# 2_MCU.net
KiCad netlist of a schematic drawn in Altium Designer
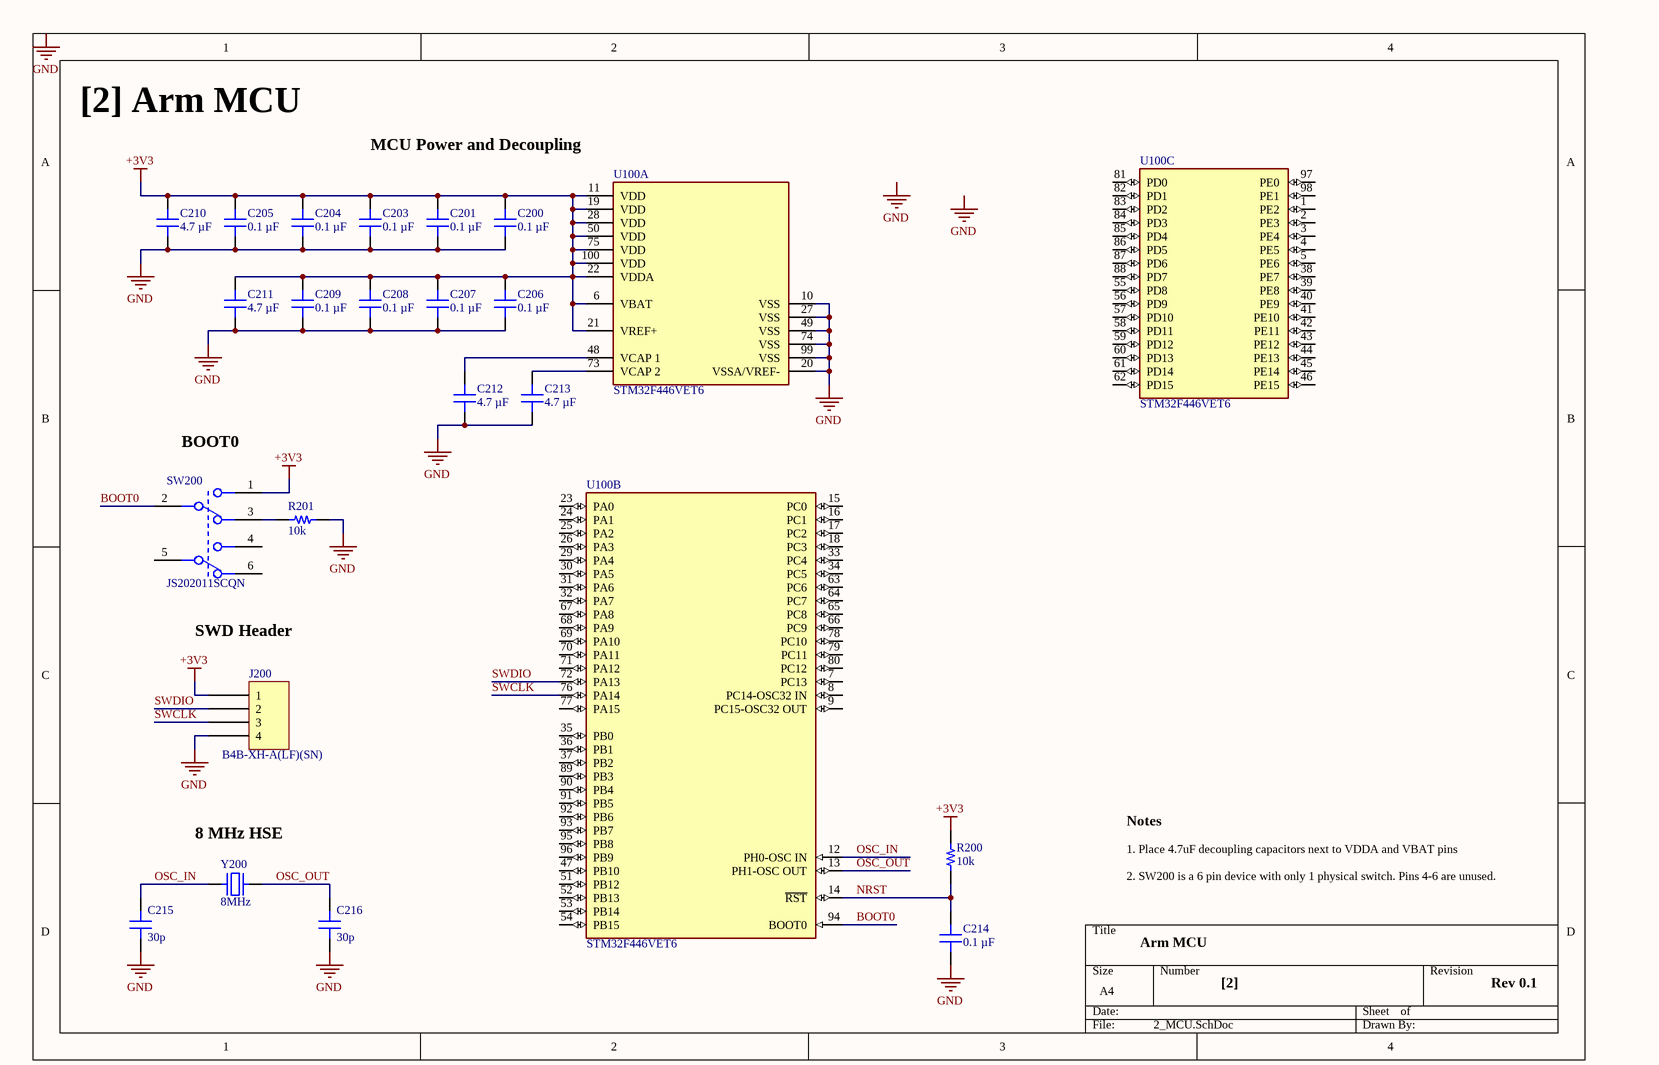
[diagram p0: 2_MCU.SchDoc]

(export (version "E")
  (design (tool "Eeschema 10.0.6"))
  (components
    (comp (ref "C200")
      (value "0.1 µF")
      (footprint "CAP 0603_1608")
      (description "CAP CER 0.1UF 50V X7R 0603")
      (fields
        (field (name "PART NUMBER") "C0603C104K5RAC7411")
        (field (name "CAPACITANCE") "0.1 µF")
        (field (name "MANUFACTURER") "KEMET")
      )
      (libsource (lib "Celestial Altium Library - altium_library") (part "Capacitor"))
    )
    (comp (ref "C201")
      (value "0.1 µF")
      (footprint "CAP 0603_1608")
      (description "CAP CER 0.1UF 50V X7R 0603")
      (fields
        (field (name "PART NUMBER") "C0603C104K5RAC7411")
        (field (name "CAPACITANCE") "0.1 µF")
        (field (name "MANUFACTURER") "KEMET")
      )
      (libsource (lib "Celestial Altium Library - altium_library") (part "Capacitor"))
    )
    (comp (ref "C203")
      (value "0.1 µF")
      (footprint "CAP 0603_1608")
      (description "CAP CER 0.1UF 50V X7R 0603")
      (fields
        (field (name "PART NUMBER") "C0603C104K5RAC7411")
        (field (name "CAPACITANCE") "0.1 µF")
        (field (name "MANUFACTURER") "KEMET")
      )
      (libsource (lib "Celestial Altium Library - altium_library") (part "Capacitor"))
    )
    (comp (ref "C204")
      (value "0.1 µF")
      (footprint "CAP 0603_1608")
      (description "CAP CER 0.1UF 50V X7R 0603")
      (fields
        (field (name "PART NUMBER") "C0603C104K5RAC7411")
        (field (name "CAPACITANCE") "0.1 µF")
        (field (name "MANUFACTURER") "KEMET")
      )
      (libsource (lib "Celestial Altium Library - altium_library") (part "Capacitor"))
    )
    (comp (ref "C205")
      (value "0.1 µF")
      (footprint "CAP 0603_1608")
      (description "CAP CER 0.1UF 50V X7R 0603")
      (fields
        (field (name "PART NUMBER") "C0603C104K5RAC7411")
        (field (name "CAPACITANCE") "0.1 µF")
        (field (name "MANUFACTURER") "KEMET")
      )
      (libsource (lib "Celestial Altium Library - altium_library") (part "Capacitor"))
    )
    (comp (ref "C206")
      (value "0.1 µF")
      (footprint "CAP 0603_1608")
      (description "CAP CER 0.1UF 50V X7R 0603")
      (fields
        (field (name "PART NUMBER") "C0603C104K5RAC7411")
        (field (name "CAPACITANCE") "0.1 µF")
        (field (name "MANUFACTURER") "KEMET")
      )
      (libsource (lib "Celestial Altium Library - altium_library") (part "Capacitor"))
    )
    (comp (ref "C207")
      (value "0.1 µF")
      (footprint "CAP 0603_1608")
      (description "CAP CER 0.1UF 50V X7R 0603")
      (fields
        (field (name "PART NUMBER") "C0603C104K5RAC7411")
        (field (name "CAPACITANCE") "0.1 µF")
        (field (name "MANUFACTURER") "KEMET")
      )
      (libsource (lib "Celestial Altium Library - altium_library") (part "Capacitor"))
    )
    (comp (ref "C208")
      (value "0.1 µF")
      (footprint "CAP 0603_1608")
      (description "CAP CER 0.1UF 50V X7R 0603")
      (fields
        (field (name "PART NUMBER") "C0603C104K5RAC7411")
        (field (name "CAPACITANCE") "0.1 µF")
        (field (name "MANUFACTURER") "KEMET")
      )
      (libsource (lib "Celestial Altium Library - altium_library") (part "Capacitor"))
    )
    (comp (ref "C209")
      (value "0.1 µF")
      (footprint "CAP 0603_1608")
      (description "CAP CER 0.1UF 50V X7R 0603")
      (fields
        (field (name "PART NUMBER") "C0603C104K5RAC7411")
        (field (name "CAPACITANCE") "0.1 µF")
        (field (name "MANUFACTURER") "KEMET")
      )
      (libsource (lib "Celestial Altium Library - altium_library") (part "Capacitor"))
    )
    (comp (ref "C210")
      (value "4.7 µF")
      (footprint "CAP 0805_2012")
      (description "CAP CER 4.7UF 25V X7R 0805")
      (fields
        (field (name "PART NUMBER") "C0805X475M3RACAUTO")
        (field (name "CAPACITANCE") "4.7 µF")
        (field (name "MANUFACTURER") "KEMET")
      )
      (libsource (lib "Celestial Altium Library - altium_library") (part "Capacitor"))
    )
    (comp (ref "C211")
      (value "4.7 µF")
      (footprint "CAP 0805_2012")
      (description "CAP CER 4.7UF 25V X7R 0805")
      (fields
        (field (name "PART NUMBER") "C0805X475M3RACAUTO")
        (field (name "CAPACITANCE") "4.7 µF")
        (field (name "MANUFACTURER") "KEMET")
      )
      (libsource (lib "Celestial Altium Library - altium_library") (part "Capacitor"))
    )
    (comp (ref "C212")
      (value "4.7 µF")
      (footprint "CAP 0805_2012")
      (description "CAP CER 4.7UF 25V X7R 0805")
      (fields
        (field (name "PART NUMBER") "C0805X475M3RACAUTO")
        (field (name "CAPACITANCE") "4.7 µF")
        (field (name "MANUFACTURER") "KEMET")
      )
      (libsource (lib "Celestial Altium Library - altium_library") (part "Capacitor"))
    )
    (comp (ref "C213")
      (value "4.7 µF")
      (footprint "CAP 0805_2012")
      (description "CAP CER 4.7UF 25V X7R 0805")
      (fields
        (field (name "PART NUMBER") "C0805X475M3RACAUTO")
        (field (name "CAPACITANCE") "4.7 µF")
        (field (name "MANUFACTURER") "KEMET")
      )
      (libsource (lib "Celestial Altium Library - altium_library") (part "Capacitor"))
    )
    (comp (ref "C214")
      (value "0.1 µF")
      (footprint "CAP 0603_1608")
      (description "CAP CER 0.1UF 50V X7R 0603")
      (fields
        (field (name "PART NUMBER") "C0603C104K5RAC7411")
        (field (name "CAPACITANCE") "0.1 µF")
        (field (name "MANUFACTURER") "KEMET")
      )
      (libsource (lib "Celestial Altium Library - altium_library") (part "Capacitor"))
    )
    (comp (ref "C215")
      (value "30p")
      (footprint "CAP 0603_1608")
      (description "CAP CER 30PF 50V C0G/NPO 0603")
      (fields (field (name "PART NUMBER") "CC0603GRNPO9BN300") (field (name "MANUFACTURER") "Yageo"))
      (libsource (lib "Celestial Altium Library - altium_library") (part "Capacitor"))
    )
    (comp (ref "C216")
      (value "30p")
      (footprint "CAP 0603_1608")
      (description "CAP CER 30PF 50V C0G/NPO 0603")
      (fields (field (name "PART NUMBER") "CC0603GRNPO9BN300") (field (name "MANUFACTURER") "Yageo"))
      (libsource (lib "Celestial Altium Library - altium_library") (part "Capacitor"))
    )
    (comp (ref "J200")
      (value "B4B-XH-A(LF)(SN)")
      (footprint "JST XH B4B-XH-A")
      (description "CONN HEADER VERT 4POS 2.5MM")
      (fields (field (name "MANUFACTURER") "JST Sales America Inc."))
      (libsource (lib "Celestial Altium Library - altium_library") (part "4 Pin"))
    )
    (comp (ref "R200")
      (value "10k")
      (footprint "RES 0603_1608")
      (description "RES 10K OHM 0.1% 1/16W 0603")
      (fields
        (field (name "PART NUMBER") "RNCS0603BKE10K0")
        (field (name "MANUFACTURER") "Stackpole Electronics Inc")
      )
      (libsource (lib "Celestial Altium Library - altium_library") (part "Resistor"))
    )
    (comp (ref "R201")
      (value "10k")
      (footprint "RES 0603_1608")
      (description "RES 10K OHM 0.1% 1/16W 0603")
      (fields
        (field (name "PART NUMBER") "RNCS0603BKE10K0")
        (field (name "MANUFACTURER") "Stackpole Electronics Inc")
      )
      (libsource (lib "Celestial Altium Library - altium_library") (part "Resistor"))
    )
    (comp (ref "SW200")
      (value "JS202011SCQN")
      (footprint "FP-JS202011SCQN-MFG")
      (description "SWITCH SLIDE DPDT 300MA 6V")
      (libsource (lib "Altium Content Vault") (part "ac99ea1af431c19115f5225061c5c88"))
    )
    (comp (ref "U100")
      (value "STM32F446VET6")
      (footprint "FP-LQFP100-1L-MFG")
      (description "IC MCU 32BIT 512KB FLASH 100LQFP")
      (fields
        (field (name "OCTOPART") "https://octopart.com/stm32f446vet6-stmicroelectronics-52642922")
        (field (name "MANUFACTURER") "STMicroelectronics")
      )
      (libsource (lib "Altium Content Vault") (part "8e3e88e6cb74ec1f9e49940598abbc7"))
    )
    (comp (ref "Y200")
      (value "8MHz")
      (footprint "TXC 9C")
      (description "CRYSTAL 8.0000MHZ 20PF SMD")
      (fields (field (name "PART NUMBER") "9C-8.000MBBK-T") (field (name "MANUFACTURER") "TXC CORPORATION"))
      (libsource (lib "Celestial Altium Library - altium_library") (part "TXC Crystal 9C"))
    )
  )
  (nets
    (net (code "1") (name "+3V3") (class "Default")
      (node (ref "C200") (pin "2") (pinfunction "2_2") (pintype "passive"))
      (node (ref "C201") (pin "2") (pinfunction "2_2") (pintype "passive"))
      (node (ref "C203") (pin "2") (pinfunction "2_2") (pintype "passive"))
      (node (ref "C204") (pin "2") (pinfunction "2_2") (pintype "passive"))
      (node (ref "C205") (pin "2") (pinfunction "2_2") (pintype "passive"))
      (node (ref "C206") (pin "2") (pinfunction "2_2") (pintype "passive"))
      (node (ref "C207") (pin "2") (pinfunction "2_2") (pintype "passive"))
      (node (ref "C208") (pin "2") (pinfunction "2_2") (pintype "passive"))
      (node (ref "C209") (pin "2") (pinfunction "2_2") (pintype "passive"))
      (node (ref "C210") (pin "2") (pinfunction "2_2") (pintype "passive"))
      (node (ref "C211") (pin "2") (pinfunction "2_2") (pintype "passive"))
      (node (ref "J200") (pin "1") (pinfunction "1_1") (pintype "passive"))
      (node (ref "R200") (pin "2") (pinfunction "2_2") (pintype "passive"))
      (node (ref "SW200") (pin "1") (pinfunction "1_1") (pintype "passive"))
      (node (ref "U100") (pin "100") (pinfunction "VDD_100") (pintype "power_in"))
      (node (ref "U100") (pin "11") (pinfunction "VDD_11") (pintype "power_in"))
      (node (ref "U100") (pin "19") (pinfunction "VDD_19") (pintype "power_in"))
      (node (ref "U100") (pin "21") (pinfunction "VREF+_21") (pintype "power_in"))
      (node (ref "U100") (pin "22") (pinfunction "VDDA_22") (pintype "power_in"))
      (node (ref "U100") (pin "28") (pinfunction "VDD_28") (pintype "power_in"))
      (node (ref "U100") (pin "50") (pinfunction "VDD_50") (pintype "power_in"))
      (node (ref "U100") (pin "6") (pinfunction "VBAT_6") (pintype "power_in"))
      (node (ref "U100") (pin "75") (pinfunction "VDD_75") (pintype "power_in"))
    )
    (net (code "2") (name "/BOOT0") (class "Default")
      (node (ref "SW200") (pin "2") (pinfunction "2_2") (pintype "passive"))
      (node (ref "U100") (pin "94") (pinfunction "BOOT0_94") (pintype "input"))
    )
    (net (code "3") (name "/NRST") (class "Default")
      (node (ref "C214") (pin "2") (pinfunction "2_2") (pintype "passive"))
      (node (ref "R200") (pin "1") (pinfunction "1_1") (pintype "passive"))
      (node (ref "U100") (pin "14") (pinfunction "~{RST}_14") (pintype "bidirectional"))
    )
    (net (code "4") (name "/OSC_IN") (class "Default")
      (node (ref "C215") (pin "2") (pinfunction "2_2") (pintype "passive"))
      (node (ref "U100") (pin "12") (pinfunction "PH0-OSC_IN_12") (pintype "input"))
      (node (ref "Y200") (pin "1") (pinfunction "1_1") (pintype "passive"))
    )
    (net (code "5") (name "/OSC_OUT") (class "Default")
      (node (ref "C216") (pin "2") (pinfunction "2_2") (pintype "passive"))
      (node (ref "U100") (pin "13") (pinfunction "PH1-OSC_OUT_13") (pintype "bidirectional"))
      (node (ref "Y200") (pin "2") (pinfunction "2_2") (pintype "passive"))
    )
    (net (code "6") (name "/SWCLK") (class "Default")
      (node (ref "J200") (pin "3") (pinfunction "3_3") (pintype "passive"))
      (node (ref "U100") (pin "76") (pinfunction "PA14_76") (pintype "bidirectional"))
    )
    (net (code "7") (name "/SWDIO") (class "Default")
      (node (ref "J200") (pin "2") (pinfunction "2_2") (pintype "passive"))
      (node (ref "U100") (pin "72") (pinfunction "PA13_72") (pintype "bidirectional"))
    )
    (net (code "8") (name "GND") (class "Default")
      (node (ref "C200") (pin "1") (pinfunction "1_1") (pintype "passive"))
      (node (ref "C201") (pin "1") (pinfunction "1_1") (pintype "passive"))
      (node (ref "C203") (pin "1") (pinfunction "1_1") (pintype "passive"))
      (node (ref "C204") (pin "1") (pinfunction "1_1") (pintype "passive"))
      (node (ref "C205") (pin "1") (pinfunction "1_1") (pintype "passive"))
      (node (ref "C206") (pin "1") (pinfunction "1_1") (pintype "passive"))
      (node (ref "C207") (pin "1") (pinfunction "1_1") (pintype "passive"))
      (node (ref "C208") (pin "1") (pinfunction "1_1") (pintype "passive"))
      (node (ref "C209") (pin "1") (pinfunction "1_1") (pintype "passive"))
      (node (ref "C210") (pin "1") (pinfunction "1_1") (pintype "passive"))
      (node (ref "C211") (pin "1") (pinfunction "1_1") (pintype "passive"))
      (node (ref "C212") (pin "1") (pinfunction "1_1") (pintype "passive"))
      (node (ref "C213") (pin "1") (pinfunction "1_1") (pintype "passive"))
      (node (ref "C214") (pin "1") (pinfunction "1_1") (pintype "passive"))
      (node (ref "C215") (pin "1") (pinfunction "1_1") (pintype "passive"))
      (node (ref "C216") (pin "1") (pinfunction "1_1") (pintype "passive"))
      (node (ref "J200") (pin "4") (pinfunction "4_4") (pintype "passive"))
      (node (ref "R201") (pin "1") (pinfunction "1_1") (pintype "passive"))
      (node (ref "U100") (pin "10") (pinfunction "VSS_10") (pintype "power_in"))
      (node (ref "U100") (pin "20") (pinfunction "VSSA/VREF-_20") (pintype "power_in"))
      (node (ref "U100") (pin "27") (pinfunction "VSS_27") (pintype "power_in"))
      (node (ref "U100") (pin "49") (pinfunction "VSS_49") (pintype "power_in"))
      (node (ref "U100") (pin "74") (pinfunction "VSS_74") (pintype "power_in"))
      (node (ref "U100") (pin "99") (pinfunction "VSS_99") (pintype "power_in"))
    )
    (net (code "9") (name "Net-(R201-Pad2)") (class "Default")
      (node (ref "R201") (pin "2") (pinfunction "2_2") (pintype "passive"))
      (node (ref "SW200") (pin "3") (pinfunction "3_3") (pintype "passive"))
    )
    (net (code "10") (name "Net-(U100A-VCAP_1)") (class "Default")
      (node (ref "C212") (pin "2") (pinfunction "2_2") (pintype "passive"))
      (node (ref "U100") (pin "48") (pinfunction "VCAP_1_48") (pintype "power_in"))
    )
    (net (code "11") (name "Net-(U100A-VCAP_2)") (class "Default")
      (node (ref "C213") (pin "2") (pinfunction "2_2") (pintype "passive"))
      (node (ref "U100") (pin "73") (pinfunction "VCAP_2_73") (pintype "power_in"))
    )
    (net (code "12") (name "unconnected-(SW200-Pad4)") (class "Default")
      (node (ref "SW200") (pin "4") (pinfunction "4_4") (pintype "passive"))
    )
    (net (code "13") (name "unconnected-(SW200-Pad5)") (class "Default")
      (node (ref "SW200") (pin "5") (pinfunction "5_5") (pintype "passive"))
    )
    (net (code "14") (name "unconnected-(SW200-Pad6)") (class "Default")
      (node (ref "SW200") (pin "6") (pinfunction "6_6") (pintype "passive"))
    )
    (net (code "15") (name "unconnected-(U100B-PA0-Pad23)") (class "Default")
      (node (ref "U100") (pin "23") (pinfunction "PA0_23") (pintype "bidirectional"))
    )
    (net (code "16") (name "unconnected-(U100B-PA1-Pad24)") (class "Default")
      (node (ref "U100") (pin "24") (pinfunction "PA1_24") (pintype "bidirectional"))
    )
    (net (code "17") (name "unconnected-(U100B-PA2-Pad25)") (class "Default")
      (node (ref "U100") (pin "25") (pinfunction "PA2_25") (pintype "bidirectional"))
    )
    (net (code "18") (name "unconnected-(U100B-PA3-Pad26)") (class "Default")
      (node (ref "U100") (pin "26") (pinfunction "PA3_26") (pintype "bidirectional"))
    )
    (net (code "19") (name "unconnected-(U100B-PA4-Pad29)") (class "Default")
      (node (ref "U100") (pin "29") (pinfunction "PA4_29") (pintype "bidirectional"))
    )
    (net (code "20") (name "unconnected-(U100B-PA5-Pad30)") (class "Default")
      (node (ref "U100") (pin "30") (pinfunction "PA5_30") (pintype "bidirectional"))
    )
    (net (code "21") (name "unconnected-(U100B-PA6-Pad31)") (class "Default")
      (node (ref "U100") (pin "31") (pinfunction "PA6_31") (pintype "bidirectional"))
    )
    (net (code "22") (name "unconnected-(U100B-PA7-Pad32)") (class "Default")
      (node (ref "U100") (pin "32") (pinfunction "PA7_32") (pintype "bidirectional"))
    )
    (net (code "23") (name "unconnected-(U100B-PA8-Pad67)") (class "Default")
      (node (ref "U100") (pin "67") (pinfunction "PA8_67") (pintype "bidirectional"))
    )
    (net (code "24") (name "unconnected-(U100B-PA9-Pad68)") (class "Default")
      (node (ref "U100") (pin "68") (pinfunction "PA9_68") (pintype "bidirectional"))
    )
    (net (code "25") (name "unconnected-(U100B-PA10-Pad69)") (class "Default")
      (node (ref "U100") (pin "69") (pinfunction "PA10_69") (pintype "bidirectional"))
    )
    (net (code "26") (name "unconnected-(U100B-PA11-Pad70)") (class "Default")
      (node (ref "U100") (pin "70") (pinfunction "PA11_70") (pintype "bidirectional"))
    )
    (net (code "27") (name "unconnected-(U100B-PA12-Pad71)") (class "Default")
      (node (ref "U100") (pin "71") (pinfunction "PA12_71") (pintype "bidirectional"))
    )
    (net (code "28") (name "unconnected-(U100B-PA15-Pad77)") (class "Default")
      (node (ref "U100") (pin "77") (pinfunction "PA15_77") (pintype "bidirectional"))
    )
    (net (code "29") (name "unconnected-(U100B-PB0-Pad35)") (class "Default")
      (node (ref "U100") (pin "35") (pinfunction "PB0_35") (pintype "bidirectional"))
    )
    (net (code "30") (name "unconnected-(U100B-PB1-Pad36)") (class "Default")
      (node (ref "U100") (pin "36") (pinfunction "PB1_36") (pintype "bidirectional"))
    )
    (net (code "31") (name "unconnected-(U100B-PB2-Pad37)") (class "Default")
      (node (ref "U100") (pin "37") (pinfunction "PB2_37") (pintype "bidirectional"))
    )
    (net (code "32") (name "unconnected-(U100B-PB3-Pad89)") (class "Default")
      (node (ref "U100") (pin "89") (pinfunction "PB3_89") (pintype "bidirectional"))
    )
    (net (code "33") (name "unconnected-(U100B-PB4-Pad90)") (class "Default")
      (node (ref "U100") (pin "90") (pinfunction "PB4_90") (pintype "bidirectional"))
    )
    (net (code "34") (name "unconnected-(U100B-PB5-Pad91)") (class "Default")
      (node (ref "U100") (pin "91") (pinfunction "PB5_91") (pintype "bidirectional"))
    )
    (net (code "35") (name "unconnected-(U100B-PB6-Pad92)") (class "Default")
      (node (ref "U100") (pin "92") (pinfunction "PB6_92") (pintype "bidirectional"))
    )
    (net (code "36") (name "unconnected-(U100B-PB7-Pad93)") (class "Default")
      (node (ref "U100") (pin "93") (pinfunction "PB7_93") (pintype "bidirectional"))
    )
    (net (code "37") (name "unconnected-(U100B-PB8-Pad95)") (class "Default")
      (node (ref "U100") (pin "95") (pinfunction "PB8_95") (pintype "bidirectional"))
    )
    (net (code "38") (name "unconnected-(U100B-PB9-Pad96)") (class "Default")
      (node (ref "U100") (pin "96") (pinfunction "PB9_96") (pintype "bidirectional"))
    )
    (net (code "39") (name "unconnected-(U100B-PB10-Pad47)") (class "Default")
      (node (ref "U100") (pin "47") (pinfunction "PB10_47") (pintype "bidirectional"))
    )
    (net (code "40") (name "unconnected-(U100B-PB12-Pad51)") (class "Default")
      (node (ref "U100") (pin "51") (pinfunction "PB12_51") (pintype "bidirectional"))
    )
    (net (code "41") (name "unconnected-(U100B-PB13-Pad52)") (class "Default")
      (node (ref "U100") (pin "52") (pinfunction "PB13_52") (pintype "bidirectional"))
    )
    (net (code "42") (name "unconnected-(U100B-PB14-Pad53)") (class "Default")
      (node (ref "U100") (pin "53") (pinfunction "PB14_53") (pintype "bidirectional"))
    )
    (net (code "43") (name "unconnected-(U100B-PB15-Pad54)") (class "Default")
      (node (ref "U100") (pin "54") (pinfunction "PB15_54") (pintype "bidirectional"))
    )
    (net (code "44") (name "unconnected-(U100B-PC0-Pad15)") (class "Default")
      (node (ref "U100") (pin "15") (pinfunction "PC0_15") (pintype "bidirectional"))
    )
    (net (code "45") (name "unconnected-(U100B-PC1-Pad16)") (class "Default")
      (node (ref "U100") (pin "16") (pinfunction "PC1_16") (pintype "bidirectional"))
    )
    (net (code "46") (name "unconnected-(U100B-PC2-Pad17)") (class "Default")
      (node (ref "U100") (pin "17") (pinfunction "PC2_17") (pintype "bidirectional"))
    )
    (net (code "47") (name "unconnected-(U100B-PC3-Pad18)") (class "Default")
      (node (ref "U100") (pin "18") (pinfunction "PC3_18") (pintype "bidirectional"))
    )
    (net (code "48") (name "unconnected-(U100B-PC4-Pad33)") (class "Default")
      (node (ref "U100") (pin "33") (pinfunction "PC4_33") (pintype "bidirectional"))
    )
    (net (code "49") (name "unconnected-(U100B-PC5-Pad34)") (class "Default")
      (node (ref "U100") (pin "34") (pinfunction "PC5_34") (pintype "bidirectional"))
    )
    (net (code "50") (name "unconnected-(U100B-PC6-Pad63)") (class "Default")
      (node (ref "U100") (pin "63") (pinfunction "PC6_63") (pintype "bidirectional"))
    )
    (net (code "51") (name "unconnected-(U100B-PC7-Pad64)") (class "Default")
      (node (ref "U100") (pin "64") (pinfunction "PC7_64") (pintype "bidirectional"))
    )
    (net (code "52") (name "unconnected-(U100B-PC8-Pad65)") (class "Default")
      (node (ref "U100") (pin "65") (pinfunction "PC8_65") (pintype "bidirectional"))
    )
    (net (code "53") (name "unconnected-(U100B-PC9-Pad66)") (class "Default")
      (node (ref "U100") (pin "66") (pinfunction "PC9_66") (pintype "bidirectional"))
    )
    (net (code "54") (name "unconnected-(U100B-PC10-Pad78)") (class "Default")
      (node (ref "U100") (pin "78") (pinfunction "PC10_78") (pintype "bidirectional"))
    )
    (net (code "55") (name "unconnected-(U100B-PC11-Pad79)") (class "Default")
      (node (ref "U100") (pin "79") (pinfunction "PC11_79") (pintype "bidirectional"))
    )
    (net (code "56") (name "unconnected-(U100B-PC12-Pad80)") (class "Default")
      (node (ref "U100") (pin "80") (pinfunction "PC12_80") (pintype "bidirectional"))
    )
    (net (code "57") (name "unconnected-(U100B-PC13-Pad7)") (class "Default")
      (node (ref "U100") (pin "7") (pinfunction "PC13_7") (pintype "bidirectional"))
    )
    (net (code "58") (name "unconnected-(U100B-PC14-OSC32_IN-Pad8)") (class "Default")
      (node (ref "U100") (pin "8") (pinfunction "PC14-OSC32_IN_8") (pintype "bidirectional"))
    )
    (net (code "59") (name "unconnected-(U100B-PC15-OSC32_OUT-Pad9)") (class "Default")
      (node (ref "U100") (pin "9") (pinfunction "PC15-OSC32_OUT_9") (pintype "bidirectional"))
    )
    (net (code "60") (name "unconnected-(U100C-PD0-Pad81)") (class "Default")
      (node (ref "U100") (pin "81") (pinfunction "PD0_81") (pintype "bidirectional"))
    )
    (net (code "61") (name "unconnected-(U100C-PD1-Pad82)") (class "Default")
      (node (ref "U100") (pin "82") (pinfunction "PD1_82") (pintype "bidirectional"))
    )
    (net (code "62") (name "unconnected-(U100C-PD2-Pad83)") (class "Default")
      (node (ref "U100") (pin "83") (pinfunction "PD2_83") (pintype "bidirectional"))
    )
    (net (code "63") (name "unconnected-(U100C-PD3-Pad84)") (class "Default")
      (node (ref "U100") (pin "84") (pinfunction "PD3_84") (pintype "bidirectional"))
    )
    (net (code "64") (name "unconnected-(U100C-PD4-Pad85)") (class "Default")
      (node (ref "U100") (pin "85") (pinfunction "PD4_85") (pintype "bidirectional"))
    )
    (net (code "65") (name "unconnected-(U100C-PD5-Pad86)") (class "Default")
      (node (ref "U100") (pin "86") (pinfunction "PD5_86") (pintype "bidirectional"))
    )
    (net (code "66") (name "unconnected-(U100C-PD6-Pad87)") (class "Default")
      (node (ref "U100") (pin "87") (pinfunction "PD6_87") (pintype "bidirectional"))
    )
    (net (code "67") (name "unconnected-(U100C-PD7-Pad88)") (class "Default")
      (node (ref "U100") (pin "88") (pinfunction "PD7_88") (pintype "bidirectional"))
    )
    (net (code "68") (name "unconnected-(U100C-PD8-Pad55)") (class "Default")
      (node (ref "U100") (pin "55") (pinfunction "PD8_55") (pintype "bidirectional"))
    )
    (net (code "69") (name "unconnected-(U100C-PD9-Pad56)") (class "Default")
      (node (ref "U100") (pin "56") (pinfunction "PD9_56") (pintype "bidirectional"))
    )
    (net (code "70") (name "unconnected-(U100C-PD10-Pad57)") (class "Default")
      (node (ref "U100") (pin "57") (pinfunction "PD10_57") (pintype "bidirectional"))
    )
    (net (code "71") (name "unconnected-(U100C-PD11-Pad58)") (class "Default")
      (node (ref "U100") (pin "58") (pinfunction "PD11_58") (pintype "bidirectional"))
    )
    (net (code "72") (name "unconnected-(U100C-PD12-Pad59)") (class "Default")
      (node (ref "U100") (pin "59") (pinfunction "PD12_59") (pintype "bidirectional"))
    )
    (net (code "73") (name "unconnected-(U100C-PD13-Pad60)") (class "Default")
      (node (ref "U100") (pin "60") (pinfunction "PD13_60") (pintype "bidirectional"))
    )
    (net (code "74") (name "unconnected-(U100C-PD14-Pad61)") (class "Default")
      (node (ref "U100") (pin "61") (pinfunction "PD14_61") (pintype "bidirectional"))
    )
    (net (code "75") (name "unconnected-(U100C-PD15-Pad62)") (class "Default")
      (node (ref "U100") (pin "62") (pinfunction "PD15_62") (pintype "bidirectional"))
    )
    (net (code "76") (name "unconnected-(U100C-PE0-Pad97)") (class "Default")
      (node (ref "U100") (pin "97") (pinfunction "PE0_97") (pintype "bidirectional"))
    )
    (net (code "77") (name "unconnected-(U100C-PE1-Pad98)") (class "Default")
      (node (ref "U100") (pin "98") (pinfunction "PE1_98") (pintype "bidirectional"))
    )
    (net (code "78") (name "unconnected-(U100C-PE2-Pad1)") (class "Default")
      (node (ref "U100") (pin "1") (pinfunction "PE2_1") (pintype "bidirectional"))
    )
    (net (code "79") (name "unconnected-(U100C-PE3-Pad2)") (class "Default")
      (node (ref "U100") (pin "2") (pinfunction "PE3_2") (pintype "bidirectional"))
    )
    (net (code "80") (name "unconnected-(U100C-PE4-Pad3)") (class "Default")
      (node (ref "U100") (pin "3") (pinfunction "PE4_3") (pintype "bidirectional"))
    )
    (net (code "81") (name "unconnected-(U100C-PE5-Pad4)") (class "Default")
      (node (ref "U100") (pin "4") (pinfunction "PE5_4") (pintype "bidirectional"))
    )
    (net (code "82") (name "unconnected-(U100C-PE6-Pad5)") (class "Default")
      (node (ref "U100") (pin "5") (pinfunction "PE6_5") (pintype "bidirectional"))
    )
    (net (code "83") (name "unconnected-(U100C-PE7-Pad38)") (class "Default")
      (node (ref "U100") (pin "38") (pinfunction "PE7_38") (pintype "bidirectional"))
    )
    (net (code "84") (name "unconnected-(U100C-PE8-Pad39)") (class "Default")
      (node (ref "U100") (pin "39") (pinfunction "PE8_39") (pintype "bidirectional"))
    )
    (net (code "85") (name "unconnected-(U100C-PE9-Pad40)") (class "Default")
      (node (ref "U100") (pin "40") (pinfunction "PE9_40") (pintype "bidirectional"))
    )
    (net (code "86") (name "unconnected-(U100C-PE10-Pad41)") (class "Default")
      (node (ref "U100") (pin "41") (pinfunction "PE10_41") (pintype "bidirectional"))
    )
    (net (code "87") (name "unconnected-(U100C-PE11-Pad42)") (class "Default")
      (node (ref "U100") (pin "42") (pinfunction "PE11_42") (pintype "bidirectional"))
    )
    (net (code "88") (name "unconnected-(U100C-PE12-Pad43)") (class "Default")
      (node (ref "U100") (pin "43") (pinfunction "PE12_43") (pintype "bidirectional"))
    )
    (net (code "89") (name "unconnected-(U100C-PE13-Pad44)") (class "Default")
      (node (ref "U100") (pin "44") (pinfunction "PE13_44") (pintype "bidirectional"))
    )
    (net (code "90") (name "unconnected-(U100C-PE14-Pad45)") (class "Default")
      (node (ref "U100") (pin "45") (pinfunction "PE14_45") (pintype "bidirectional"))
    )
    (net (code "91") (name "unconnected-(U100C-PE15-Pad46)") (class "Default")
      (node (ref "U100") (pin "46") (pinfunction "PE15_46") (pintype "bidirectional"))
    )
  )
)
